# TH8_CPU_STM32F4.net
KiCad netlist of a schematic drawn in Altium Designer
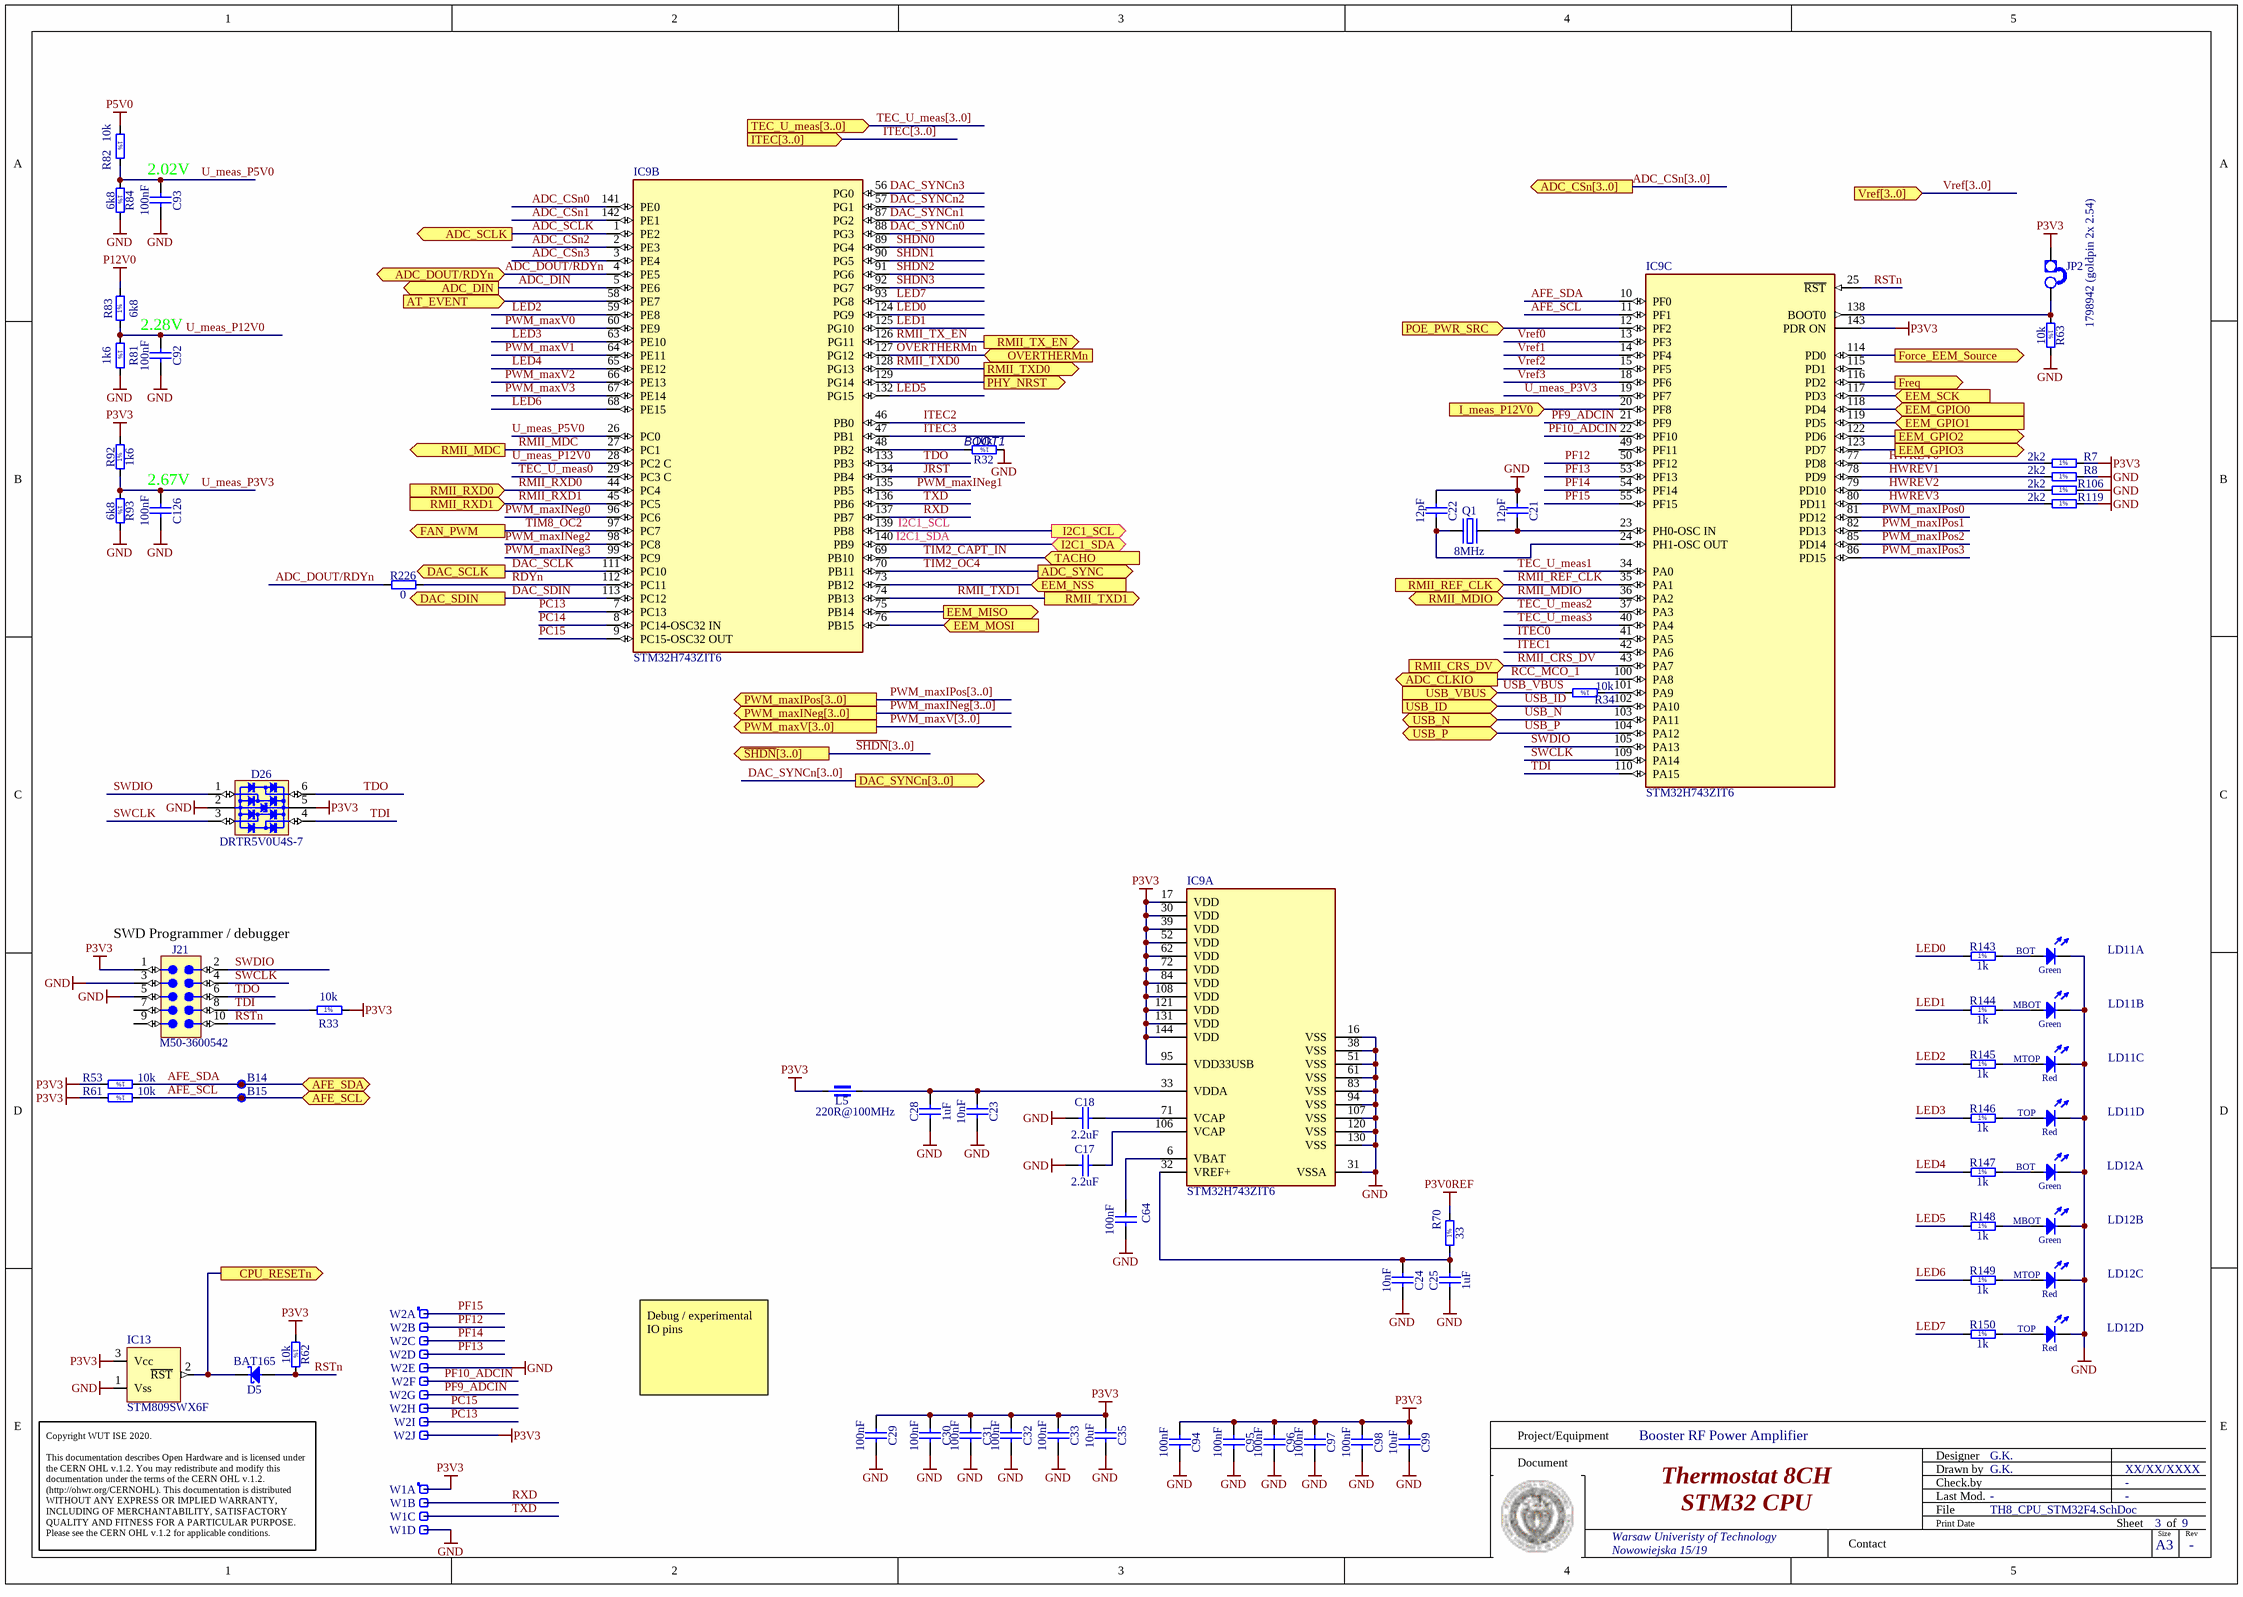
[diagram p0: TH8_CPU_STM32F4.SchDoc]

(export (version "E")
  (design (tool "Eeschema 10.0.6"))
  (components
    (comp (ref "B14")
      (value "SMD Pad")
      (footprint "C100")
      (description "Through Hole Pad")
      (fields (field (name "PART NUMBER") "SMD_PAD_D1MM") (field (name "AUTHOR") "CERN DEM JLC"))
      (libsource (lib "Eletro-mechanical") (part "Single SMD Pad (Round)"))
    )
    (comp (ref "B15")
      (value "SMD Pad")
      (footprint "C100")
      (description "Through Hole Pad")
      (fields (field (name "PART NUMBER") "SMD_PAD_D1MM") (field (name "AUTHOR") "CERN DEM JLC"))
      (libsource (lib "Eletro-mechanical") (part "Single SMD Pad (Round)"))
    )
    (comp (ref "C17")
      (value "2.2uF")
      (footprint "CAPC1608X90N")
      (description "Non-polarised capacitor")
      (fields
        (field (name "PART NUMBER") "CC0603_2.2UF_10V_20%_X7R")
        (field (name "VOLTAGE") "10V")
        (field (name "AUTHOR") "CERN DEM JLC")
      )
      (libsource (lib "Capacitors") (part "Capacitor - non polarized"))
    )
    (comp (ref "C18")
      (value "2.2uF")
      (footprint "CAPC1608X90N")
      (description "Non-polarised capacitor")
      (fields
        (field (name "PART NUMBER") "CC0603_2.2UF_10V_20%_X7R")
        (field (name "VOLTAGE") "10V")
        (field (name "AUTHOR") "CERN DEM JLC")
      )
      (libsource (lib "Capacitors") (part "Capacitor - non polarized"))
    )
    (comp (ref "C21")
      (value "12pF")
      (footprint "CAPC1005X55N")
      (description "Non-polarised capacitor")
      (fields
        (field (name "PART NUMBER") "CC0402_12PF_50V_5%_C0G")
        (field (name "VOLTAGE") "50V")
        (field (name "AUTHOR") "CERN DEM JLC")
      )
      (libsource (lib "Capacitors") (part "Capacitor - non polarized"))
    )
    (comp (ref "C22")
      (value "12pF")
      (footprint "CAPC1005X55N")
      (description "Non-polarised capacitor")
      (fields
        (field (name "PART NUMBER") "CC0402_12PF_50V_5%_C0G")
        (field (name "VOLTAGE") "50V")
        (field (name "AUTHOR") "CERN DEM JLC")
      )
      (libsource (lib "Capacitors") (part "Capacitor - non polarized"))
    )
    (comp (ref "C23")
      (value "10nF")
      (footprint "CAPC1005X55N")
      (description "Non-polarised capacitor")
      (fields
        (field (name "PART NUMBER") "CC0402_10NF_16V_10%_X7R")
        (field (name "VOLTAGE") "16V")
        (field (name "AUTHOR") "CERN DEM JLC")
      )
      (libsource (lib "Capacitors") (part "Capacitor - non polarized"))
    )
    (comp (ref "C24")
      (value "10nF")
      (footprint "CAPC1005X55N")
      (description "Non-polarised capacitor")
      (fields
        (field (name "PART NUMBER") "CC0402_10NF_16V_10%_X7R")
        (field (name "VOLTAGE") "16V")
        (field (name "AUTHOR") "CERN DEM JLC")
      )
      (libsource (lib "Capacitors") (part "Capacitor - non polarized"))
    )
    (comp (ref "C25")
      (value "1uF")
      (footprint "CAPC2012X110N")
      (description "Non-polarised capacitor")
      (fields
        (field (name "PART NUMBER") "CC0805_1UF_50V_10%_X7R")
        (field (name "VOLTAGE") "50V")
        (field (name "AUTHOR") "CERN DEM JLC")
      )
      (libsource (lib "Capacitors") (part "Capacitor - non polarized"))
    )
    (comp (ref "C28")
      (value "1uF")
      (footprint "CAPC2012X110N")
      (description "Non-polarised capacitor")
      (fields
        (field (name "PART NUMBER") "CC0805_1UF_50V_10%_X7R")
        (field (name "VOLTAGE") "50V")
        (field (name "AUTHOR") "CERN DEM JLC")
      )
      (libsource (lib "Capacitors") (part "Capacitor - non polarized"))
    )
    (comp (ref "C29")
      (value "100nF")
      (footprint "CAPC1005X55N")
      (description "Non-polarised capacitor")
      (fields
        (field (name "PART NUMBER") "CC0402_100NF_16V_10%_X7R")
        (field (name "VOLTAGE") "16V")
        (field (name "AUTHOR") "CERN DEM JLC")
      )
      (libsource (lib "Capacitors") (part "Capacitor - non polarized"))
    )
    (comp (ref "C30")
      (value "100nF")
      (footprint "CAPC1005X55N")
      (description "Non-polarised capacitor")
      (fields
        (field (name "PART NUMBER") "CC0402_100NF_16V_10%_X7R")
        (field (name "VOLTAGE") "16V")
        (field (name "AUTHOR") "CERN DEM JLC")
      )
      (libsource (lib "Capacitors") (part "Capacitor - non polarized"))
    )
    (comp (ref "C31")
      (value "100nF")
      (footprint "CAPC1005X55N")
      (description "Non-polarised capacitor")
      (fields
        (field (name "PART NUMBER") "CC0402_100NF_16V_10%_X7R")
        (field (name "VOLTAGE") "16V")
        (field (name "AUTHOR") "CERN DEM JLC")
      )
      (libsource (lib "Capacitors") (part "Capacitor - non polarized"))
    )
    (comp (ref "C32")
      (value "100nF")
      (footprint "CAPC1005X55N")
      (description "Non-polarised capacitor")
      (fields
        (field (name "PART NUMBER") "CC0402_100NF_16V_10%_X7R")
        (field (name "VOLTAGE") "16V")
        (field (name "AUTHOR") "CERN DEM JLC")
      )
      (libsource (lib "Capacitors") (part "Capacitor - non polarized"))
    )
    (comp (ref "C33")
      (value "100nF")
      (footprint "CAPC1005X55N")
      (description "Non-polarised capacitor")
      (fields
        (field (name "PART NUMBER") "CC0402_100NF_16V_10%_X7R")
        (field (name "VOLTAGE") "16V")
        (field (name "AUTHOR") "CERN DEM JLC")
      )
      (libsource (lib "Capacitors") (part "Capacitor - non polarized"))
    )
    (comp (ref "C35")
      (value "10uF")
      (footprint "CAPC2012X135N")
      (description "Non-polarised capacitor")
      (fields
        (field (name "PART NUMBER") "CC0805_10UF_16V_10%_X5R")
        (field (name "VOLTAGE") "16V")
        (field (name "AUTHOR") "CERN DEM JLC")
      )
      (libsource (lib "Capacitors") (part "Capacitor - non polarized"))
    )
    (comp (ref "C64")
      (value "100nF")
      (footprint "CAPC1005X55N")
      (description "Non-polarised capacitor")
      (fields
        (field (name "PART NUMBER") "CC0402_100NF_16V_10%_X7R")
        (field (name "VOLTAGE") "16V")
        (field (name "AUTHOR") "CERN DEM JLC")
      )
      (libsource (lib "Capacitors") (part "Capacitor - non polarized"))
    )
    (comp (ref "C92")
      (value "100nF")
      (footprint "CAPC1005X55N")
      (description "Non-polarised capacitor")
      (fields
        (field (name "PART NUMBER") "CC0402_100NF_16V_10%_X5R")
        (field (name "VOLTAGE") "16V")
        (field (name "AUTHOR") "CERN DEM JLC")
      )
      (libsource (lib "Capacitors") (part "Capacitor - non polarized"))
    )
    (comp (ref "C93")
      (value "100nF")
      (footprint "CAPC1005X55N")
      (description "Non-polarised capacitor")
      (fields
        (field (name "PART NUMBER") "CC0402_100NF_16V_10%_X5R")
        (field (name "VOLTAGE") "16V")
        (field (name "AUTHOR") "CERN DEM JLC")
      )
      (libsource (lib "Capacitors") (part "Capacitor - non polarized"))
    )
    (comp (ref "C94")
      (value "100nF")
      (footprint "CAPC1005X55N")
      (description "Non-polarised capacitor")
      (fields
        (field (name "PART NUMBER") "CC0402_100NF_16V_10%_X7R")
        (field (name "VOLTAGE") "16V")
        (field (name "AUTHOR") "CERN DEM JLC")
      )
      (libsource (lib "Capacitors") (part "Capacitor - non polarized"))
    )
    (comp (ref "C95")
      (value "100nF")
      (footprint "CAPC1005X55N")
      (description "Non-polarised capacitor")
      (fields
        (field (name "PART NUMBER") "CC0402_100NF_16V_10%_X7R")
        (field (name "VOLTAGE") "16V")
        (field (name "AUTHOR") "CERN DEM JLC")
      )
      (libsource (lib "Capacitors") (part "Capacitor - non polarized"))
    )
    (comp (ref "C96")
      (value "100nF")
      (footprint "CAPC1005X55N")
      (description "Non-polarised capacitor")
      (fields
        (field (name "PART NUMBER") "CC0402_100NF_16V_10%_X7R")
        (field (name "VOLTAGE") "16V")
        (field (name "AUTHOR") "CERN DEM JLC")
      )
      (libsource (lib "Capacitors") (part "Capacitor - non polarized"))
    )
    (comp (ref "C97")
      (value "100nF")
      (footprint "CAPC1005X55N")
      (description "Non-polarised capacitor")
      (fields
        (field (name "PART NUMBER") "CC0402_100NF_16V_10%_X7R")
        (field (name "VOLTAGE") "16V")
        (field (name "AUTHOR") "CERN DEM JLC")
      )
      (libsource (lib "Capacitors") (part "Capacitor - non polarized"))
    )
    (comp (ref "C98")
      (value "100nF")
      (footprint "CAPC1005X55N")
      (description "Non-polarised capacitor")
      (fields
        (field (name "PART NUMBER") "CC0402_100NF_16V_10%_X7R")
        (field (name "VOLTAGE") "16V")
        (field (name "AUTHOR") "CERN DEM JLC")
      )
      (libsource (lib "Capacitors") (part "Capacitor - non polarized"))
    )
    (comp (ref "C99")
      (value "10uF")
      (footprint "CAPC2012X135N")
      (description "Non-polarised capacitor")
      (fields
        (field (name "PART NUMBER") "CC0805_10UF_16V_10%_X5R")
        (field (name "VOLTAGE") "16V")
        (field (name "AUTHOR") "CERN DEM JLC")
      )
      (libsource (lib "Capacitors") (part "Capacitor - non polarized"))
    )
    (comp (ref "C126")
      (value "100nF")
      (footprint "CAPC1005X55N")
      (description "Non-polarised capacitor")
      (fields
        (field (name "PART NUMBER") "CC0402_100NF_16V_10%_X5R")
        (field (name "VOLTAGE") "16V")
        (field (name "AUTHOR") "CERN DEM JLC")
      )
      (libsource (lib "Capacitors") (part "Capacitor - non polarized"))
    )
    (comp (ref "D5")
      (value "BAT165")
      (footprint "SOD2512X110N")
      (description "Schottky Diode")
      (fields
        (field (name "VOLTAGE") "40V")
        (field (name "POWER") "750mA")
        (field (name "AUTHOR") "CERN DEM JLC")
      )
      (libsource (lib "ICs And Semiconductors") (part "Diode Schottky"))
    )
    (comp (ref "D26")
      (value "DRTR5V0U4S-7")
      (footprint "SOT65P210X110-6N")
      (description "Integrated Quad Ultra-Low Capacitance ESD Protection")
      (fields (field (name "MANUFACTURER") "DIODES") (field (name "AUTHOR") "GK"))
      (libsource (lib "Diodes") (part "D_TVS_DRTR5V0U4S-7"))
    )
    (comp (ref "IC9")
      (value "STM32H743ZIT6")
      (footprint "FP-LQFP144-1A-MFG")
      (description "IC MCU 32BIT 2MB FLASH 144LQFP")
      (fields
        (field (name "MANUFACTURER") "STMicroelectronics")
        (field (name "OCTOPART") "https://octopart.com/stm32h743zit6-stmicroelectronics-76372529")
      )
      (libsource (lib "Altium Content Vault") (part "4977c5c7f8d170b58ef15f889e64ba1"))
    )
    (comp (ref "IC13")
      (value "STM809SWX6F")
      (footprint "SOT-23")
      (description "2.93V  Reset circuit")
      (libsource (lib "LIBRARY_SCH") (part "VMON_STM809"))
    )
    (comp (ref "J21")
      (value "Header 10")
      (footprint "HARWIN_M50-3600542")
      (description "10 Contacts - Pitch 1.27mm - Dual Row SMT Vertical Pin Header (Post Lead = 3mm, Insulator 1mm)")
      (fields
        (field (name "PART NUMBER") "HARWIN_M50-3600542")
        (field (name "MANUFACTURER") "HARWIN")
        (field (name "MANUFACTURER PART NUMBER") "M50-3600542")
        (field (name "AUTHOR") "GK")
      )
      (libsource (lib "Connectors") (part "CON_2x10 1.27 SMT_male_HARWIN"))
    )
    (comp (ref "JP2")
      (value "1798942 (goldpin 2x 2.54)")
      (footprint "jump")
      (description "Jumper")
      (libsource (lib "LIBRARY_SCH") (part "JUMPER"))
    )
    (comp (ref "L5")
      (value "220R@100MHz")
      (footprint "INDC1005X55N")
      (fields
        (field (name "PART NUMBER") "IND0402_MURATA_BLM15HB221SN1")
        (field (name "POWER") "250mA")
        (field (name "TOLERANCE") "±25%")
        (field (name "AUTHOR") "CERN DEM JLC")
      )
      (libsource (lib "Inductors & Transformers") (part "Ferrite Bead"))
    )
    (comp (ref "LD11")
      (value "Green/Green/HeRed/HeRed")
      (footprint "LED_BIVAR_H485CHHGGDL")
      (description "LED x4 G-1C2A-BOT_G-3C4A_H-5C6A_H-7C8A-TOP")
      (fields
        (field (name "PART NUMBER") "LED_BIVAR_H485CHHGGDL")
        (field (name "MANUFACTURER") "BIVAR")
        (field (name "AUTHOR") "CERN DEM BC")
      )
      (libsource (lib "ICs And Semiconductors") (part "LED x4 G-1C2A-BOT_G-3C4A_H-5C6A_H-7C8A-TOP"))
    )
    (comp (ref "LD12")
      (value "Green/Green/HeRed/HeRed")
      (footprint "LED_BIVAR_H485CHHGGDL")
      (description "LED x4 G-1C2A-BOT_G-3C4A_H-5C6A_H-7C8A-TOP")
      (fields
        (field (name "PART NUMBER") "LED_BIVAR_H485CHHGGDL")
        (field (name "MANUFACTURER") "BIVAR")
        (field (name "AUTHOR") "CERN DEM BC")
      )
      (libsource (lib "ICs And Semiconductors") (part "LED x4 G-1C2A-BOT_G-3C4A_H-5C6A_H-7C8A-TOP"))
    )
    (comp (ref "Q1")
      (value "8MHz")
      (footprint "XTAL_TXC_7A")
      (description "Quartz Crystal")
      (fields
        (field (name "PART NUMBER") "XTAL_8MHZ_TXC_7A-8.000MAAE-T")
        (field (name "MANUFACTURER") "TXC CORPORATION")
        (field (name "AUTHOR") "CERN DEM JLC")
      )
      (libsource (lib "ICs And Semiconductors") (part "Quartz Crystal"))
    )
    (comp (ref "R7")
      (value "2k2")
      (footprint "RESC1005X40N")
      (description "Resistor - 1%")
      (fields
        (field (name "PART NUMBER") "R0402_2K2_1%_0.0625W_100PPM")
        (field (name "POWER") "0.0625W")
        (field (name "AUTHOR") "CERN DEM JLC")
      )
      (libsource (lib "Resistors") (part "Resistor - 1%"))
    )
    (comp (ref "R8")
      (value "2k2")
      (footprint "RESC1005X40N")
      (description "Resistor - 1%")
      (fields
        (field (name "PART NUMBER") "R0402_2K2_1%_0.0625W_100PPM")
        (field (name "POWER") "0.0625W")
        (field (name "AUTHOR") "CERN DEM JLC")
      )
      (libsource (lib "Resistors") (part "Resistor - 1%"))
    )
    (comp (ref "R32")
      (value "10k")
      (footprint "RESC1005X40N")
      (description "Resistor - 1%")
      (fields
        (field (name "PART NUMBER") "R0402_10K_1%_0.0625W_100PPM")
        (field (name "POWER") "0.0625W")
        (field (name "AUTHOR") "CERN DEM JLC")
      )
      (libsource (lib "Resistors") (part "Resistor - 1%"))
    )
    (comp (ref "R33")
      (value "10k")
      (footprint "RESC1005X40N")
      (description "Resistor - 1%")
      (fields
        (field (name "PART NUMBER") "R0402_10K_1%_0.0625W_100PPM")
        (field (name "POWER") "0.0625W")
        (field (name "AUTHOR") "CERN DEM JLC")
      )
      (libsource (lib "Resistors") (part "Resistor - 1%"))
    )
    (comp (ref "R34")
      (value "10k")
      (footprint "RESC1005X40N")
      (description "Resistor - 1%")
      (fields
        (field (name "PART NUMBER") "R0402_10K_1%_0.0625W_100PPM")
        (field (name "POWER") "0.0625W")
        (field (name "AUTHOR") "CERN DEM JLC")
      )
      (libsource (lib "Resistors") (part "Resistor - 1%"))
    )
    (comp (ref "R53")
      (value "10k")
      (footprint "RESC1005X40N")
      (description "Resistor - 1%")
      (fields
        (field (name "PART NUMBER") "R0402_10K_1%_0.0625W_100PPM")
        (field (name "POWER") "0.0625W")
        (field (name "AUTHOR") "CERN DEM JLC")
      )
      (libsource (lib "Resistors") (part "Resistor - 1%"))
    )
    (comp (ref "R61")
      (value "10k")
      (footprint "RESC1005X40N")
      (description "Resistor - 1%")
      (fields
        (field (name "PART NUMBER") "R0402_10K_1%_0.0625W_100PPM")
        (field (name "POWER") "0.0625W")
        (field (name "AUTHOR") "CERN DEM JLC")
      )
      (libsource (lib "Resistors") (part "Resistor - 1%"))
    )
    (comp (ref "R62")
      (value "10k")
      (footprint "RESC1005X40N")
      (description "Resistor - 1%")
      (fields
        (field (name "PART NUMBER") "R0402_10K_1%_0.0625W_100PPM")
        (field (name "POWER") "0.0625W")
        (field (name "AUTHOR") "CERN DEM JLC")
      )
      (libsource (lib "Resistors") (part "Resistor - 1%"))
    )
    (comp (ref "R63")
      (value "10k")
      (footprint "RESC1005X40N")
      (description "Resistor - 1%")
      (fields
        (field (name "PART NUMBER") "R0402_10K_1%_0.0625W_100PPM")
        (field (name "POWER") "0.0625W")
        (field (name "AUTHOR") "CERN DEM JLC")
      )
      (libsource (lib "Resistors") (part "Resistor - 1%"))
    )
    (comp (ref "R70")
      (value "33")
      (footprint "RESC1005X40N")
      (description "Resistor - 1%")
      (fields
        (field (name "PART NUMBER") "R0402_33R_1%_0.0625W_100PPM")
        (field (name "POWER") "0.0625W")
        (field (name "AUTHOR") "CERN DEM JLC")
      )
      (libsource (lib "Resistors") (part "Resistor - 1%"))
    )
    (comp (ref "R81")
      (value "1k6")
      (footprint "RESC1005X40N")
      (description "Resistor - 1%")
      (fields
        (field (name "PART NUMBER") "R0402_1K6_1%_0.0625W_100PPM")
        (field (name "POWER") "0.0625W")
        (field (name "AUTHOR") "CERN DEM JLC")
      )
      (libsource (lib "Resistors") (part "Resistor - 1%"))
    )
    (comp (ref "R82")
      (value "10k")
      (footprint "RESC1005X40N")
      (description "Resistor - 1%")
      (fields
        (field (name "PART NUMBER") "R0402_10K_1%_0.0625W_100PPM")
        (field (name "POWER") "0.0625W")
        (field (name "AUTHOR") "CERN DEM JLC")
      )
      (libsource (lib "Resistors") (part "Resistor - 1%"))
    )
    (comp (ref "R83")
      (value "6k8")
      (footprint "RESC1005X40N")
      (description "Resistor - 1%")
      (fields
        (field (name "PART NUMBER") "R0402_6K8_1%_0.0625W_100PPM")
        (field (name "POWER") "0.0625W")
        (field (name "AUTHOR") "CERN DEM JLC")
      )
      (libsource (lib "Resistors") (part "Resistor - 1%"))
    )
    (comp (ref "R84")
      (value "6k8")
      (footprint "RESC1005X40N")
      (description "Resistor - 1%")
      (fields
        (field (name "PART NUMBER") "R0402_6K8_1%_0.0625W_100PPM")
        (field (name "POWER") "0.0625W")
        (field (name "AUTHOR") "CERN DEM JLC")
      )
      (libsource (lib "Resistors") (part "Resistor - 1%"))
    )
    (comp (ref "R92")
      (value "1k6")
      (footprint "RESC1005X40N")
      (description "Resistor - 1%")
      (fields
        (field (name "PART NUMBER") "R0402_1K6_1%_0.0625W_100PPM")
        (field (name "POWER") "0.0625W")
        (field (name "AUTHOR") "CERN DEM JLC")
      )
      (libsource (lib "Resistors") (part "Resistor - 1%"))
    )
    (comp (ref "R93")
      (value "6k8")
      (footprint "RESC1005X40N")
      (description "Resistor - 1%")
      (fields
        (field (name "PART NUMBER") "R0402_6K8_1%_0.0625W_100PPM")
        (field (name "POWER") "0.0625W")
        (field (name "AUTHOR") "CERN DEM JLC")
      )
      (libsource (lib "Resistors") (part "Resistor - 1%"))
    )
    (comp (ref "R106")
      (value "2k2")
      (footprint "RESC1005X40N")
      (description "Resistor - 1%")
      (fields
        (field (name "PART NUMBER") "R0402_2K2_1%_0.0625W_100PPM")
        (field (name "POWER") "0.0625W")
        (field (name "AUTHOR") "CERN DEM JLC")
      )
      (libsource (lib "Resistors") (part "Resistor - 1%"))
    )
    (comp (ref "R119")
      (value "2k2")
      (footprint "RESC1005X40N")
      (description "Resistor - 1%")
      (fields
        (field (name "PART NUMBER") "R0402_2K2_1%_0.0625W_100PPM")
        (field (name "POWER") "0.0625W")
        (field (name "AUTHOR") "CERN DEM JLC")
      )
      (libsource (lib "Resistors") (part "Resistor - 1%"))
    )
    (comp (ref "R143")
      (value "1k")
      (footprint "RESC1005X40N")
      (description "Resistor - 1%")
      (fields
        (field (name "PART NUMBER") "R0402_1K_1%_0.0625W_100PPM")
        (field (name "POWER") "0.0625W")
        (field (name "AUTHOR") "CERN DEM JLC")
      )
      (libsource (lib "Resistors") (part "Resistor - 1%"))
    )
    (comp (ref "R144")
      (value "1k")
      (footprint "RESC1005X40N")
      (description "Resistor - 1%")
      (fields
        (field (name "PART NUMBER") "R0402_1K_1%_0.0625W_100PPM")
        (field (name "POWER") "0.0625W")
        (field (name "AUTHOR") "CERN DEM JLC")
      )
      (libsource (lib "Resistors") (part "Resistor - 1%"))
    )
    (comp (ref "R145")
      (value "1k")
      (footprint "RESC1005X40N")
      (description "Resistor - 1%")
      (fields
        (field (name "PART NUMBER") "R0402_1K_1%_0.0625W_100PPM")
        (field (name "POWER") "0.0625W")
        (field (name "AUTHOR") "CERN DEM JLC")
      )
      (libsource (lib "Resistors") (part "Resistor - 1%"))
    )
    (comp (ref "R146")
      (value "1k")
      (footprint "RESC1005X40N")
      (description "Resistor - 1%")
      (fields
        (field (name "PART NUMBER") "R0402_1K_1%_0.0625W_100PPM")
        (field (name "POWER") "0.0625W")
        (field (name "AUTHOR") "CERN DEM JLC")
      )
      (libsource (lib "Resistors") (part "Resistor - 1%"))
    )
    (comp (ref "R147")
      (value "1k")
      (footprint "RESC1005X40N")
      (description "Resistor - 1%")
      (fields
        (field (name "PART NUMBER") "R0402_1K_1%_0.0625W_100PPM")
        (field (name "POWER") "0.0625W")
        (field (name "AUTHOR") "CERN DEM JLC")
      )
      (libsource (lib "Resistors") (part "Resistor - 1%"))
    )
    (comp (ref "R148")
      (value "1k")
      (footprint "RESC1005X40N")
      (description "Resistor - 1%")
      (fields
        (field (name "PART NUMBER") "R0402_1K_1%_0.0625W_100PPM")
        (field (name "POWER") "0.0625W")
        (field (name "AUTHOR") "CERN DEM JLC")
      )
      (libsource (lib "Resistors") (part "Resistor - 1%"))
    )
    (comp (ref "R149")
      (value "1k")
      (footprint "RESC1005X40N")
      (description "Resistor - 1%")
      (fields
        (field (name "PART NUMBER") "R0402_1K_1%_0.0625W_100PPM")
        (field (name "POWER") "0.0625W")
        (field (name "AUTHOR") "CERN DEM JLC")
      )
      (libsource (lib "Resistors") (part "Resistor - 1%"))
    )
    (comp (ref "R150")
      (value "1k")
      (footprint "RESC1005X40N")
      (description "Resistor - 1%")
      (fields
        (field (name "PART NUMBER") "R0402_1K_1%_0.0625W_100PPM")
        (field (name "POWER") "0.0625W")
        (field (name "AUTHOR") "CERN DEM JLC")
      )
      (libsource (lib "Resistors") (part "Resistor - 1%"))
    )
    (comp (ref "R226")
      (value "0")
      (footprint "RESC1005X40N")
      (description "Resistor")
      (fields
        (field (name "PART NUMBER") "R0402_0R_JUMPER")
        (field (name "MANUFACTURER") "GENERIC")
        (field (name "AUTHOR") "CERN DEM JLC")
      )
      (libsource (lib "Resistors") (part "Resistor"))
    )
    (comp (ref "W1")
      (value "Header 4")
      (footprint "SAMTEC_HTSW-104-23-L-S")
      (description "4 Mini Wire-Wrap Contact Strip Header")
      (fields
        (field (name "PART NUMBER") "SAMTEC_HTSW-104-23-L-S")
        (field (name "MANUFACTURER") "SAMTEC")
        (field (name "AUTHOR") "CERN DEM JLC")
      )
      (libsource (lib "Connectors") (part "Wire-Wrap Contact x4"))
    )
    (comp (ref "W2")
      (value "Header 10")
      (footprint "SAMTEC_MTLW-110-07-L-S-250")
      (description "10 Mini Wire-Wrap Contact Strip Header")
      (fields
        (field (name "PART NUMBER") "SAMTEC_MTLW-110-07-L-S-250")
        (field (name "MANUFACTURER") "SAMTEC")
        (field (name "AUTHOR") "CERN DEM JLC")
      )
      (libsource (lib "Connectors") (part "Wire-Wrap Contact x10"))
    )
  )
  (nets
    (net (code "1") (name "/ADC_CSn0") (class "Default")
      (node (ref "IC9") (pin "141") (pinfunction "PE0_141") (pintype "bidirectional"))
    )
    (net (code "2") (name "/ADC_CSn1") (class "Default")
      (node (ref "IC9") (pin "142") (pinfunction "PE1_142") (pintype "bidirectional"))
    )
    (net (code "3") (name "/ADC_CSn2") (class "Default")
      (node (ref "IC9") (pin "2") (pinfunction "PE3_2") (pintype "bidirectional"))
    )
    (net (code "4") (name "/ADC_CSn3") (class "Default")
      (node (ref "IC9") (pin "3") (pinfunction "PE4_3") (pintype "bidirectional"))
    )
    (net (code "6") (name "/ADC_DIN") (class "Default")
      (node (ref "IC9") (pin "5") (pinfunction "PE6_5") (pintype "bidirectional"))
    )
    (net (code "7") (name "/ADC_DOUT{slash}RDYn") (class "Default")
      (node (ref "IC9") (pin "4") (pinfunction "PE5_4") (pintype "bidirectional"))
      (node (ref "R226") (pin "1") (pinfunction "1_1") (pintype "passive"))
    )
    (net (code "8") (name "/ADC_SCLK") (class "Default")
      (node (ref "IC9") (pin "1") (pinfunction "PE2_1") (pintype "bidirectional"))
    )
    (net (code "9") (name "/AFE_SCL") (class "Default")
      (node (ref "B15") (pin "1") (pinfunction "1_1") (pintype "bidirectional"))
      (node (ref "IC9") (pin "11") (pinfunction "PF1_11") (pintype "bidirectional"))
      (node (ref "R61") (pin "1") (pinfunction "1_1") (pintype "passive"))
    )
    (net (code "10") (name "/AFE_SDA") (class "Default")
      (node (ref "B14") (pin "1") (pinfunction "1_1") (pintype "bidirectional"))
      (node (ref "IC9") (pin "10") (pinfunction "PF0_10") (pintype "bidirectional"))
      (node (ref "R53") (pin "1") (pinfunction "1_1") (pintype "passive"))
    )
    (net (code "11") (name "/AT_EVENT") (class "Default")
      (node (ref "IC9") (pin "58") (pinfunction "PE7_58") (pintype "bidirectional"))
    )
    (net (code "12") (name "/CPU_RESETn") (class "Default")
      (node (ref "D5") (pin "1") (pinfunction "C_1") (pintype "passive"))
      (node (ref "IC13") (pin "2") (pinfunction "~{RST}_2") (pintype "output"))
    )
    (net (code "13") (name "/DAC_SCLK") (class "Default")
      (node (ref "IC9") (pin "111") (pinfunction "PC10_111") (pintype "bidirectional"))
    )
    (net (code "14") (name "/DAC_SDIN") (class "Default")
      (node (ref "IC9") (pin "113") (pinfunction "PC12_113") (pintype "bidirectional"))
    )
    (net (code "15") (name "/DAC_SYNCn0") (class "Default")
      (node (ref "IC9") (pin "88") (pinfunction "PG3_88") (pintype "bidirectional"))
    )
    (net (code "16") (name "/DAC_SYNCn1") (class "Default")
      (node (ref "IC9") (pin "87") (pinfunction "PG2_87") (pintype "bidirectional"))
    )
    (net (code "17") (name "/DAC_SYNCn2") (class "Default")
      (node (ref "IC9") (pin "57") (pinfunction "PG1_57") (pintype "bidirectional"))
    )
    (net (code "18") (name "/DAC_SYNCn3") (class "Default")
      (node (ref "IC9") (pin "56") (pinfunction "PG0_56") (pintype "bidirectional"))
    )
    (net (code "20") (name "/EEM_GPIO0") (class "Default")
      (node (ref "IC9") (pin "118") (pinfunction "PD4_118") (pintype "bidirectional"))
    )
    (net (code "21") (name "/EEM_GPIO1") (class "Default")
      (node (ref "IC9") (pin "119") (pinfunction "PD5_119") (pintype "bidirectional"))
    )
    (net (code "22") (name "/EEM_GPIO2") (class "Default")
      (node (ref "IC9") (pin "122") (pinfunction "PD6_122") (pintype "bidirectional"))
    )
    (net (code "23") (name "/EEM_GPIO3") (class "Default")
      (node (ref "IC9") (pin "123") (pinfunction "PD7_123") (pintype "bidirectional"))
    )
    (net (code "24") (name "/EEM_MISO") (class "Default")
      (node (ref "IC9") (pin "75") (pinfunction "PB14_75") (pintype "bidirectional"))
    )
    (net (code "25") (name "/EEM_MOSI") (class "Default")
      (node (ref "IC9") (pin "76") (pinfunction "PB15_76") (pintype "bidirectional"))
    )
    (net (code "26") (name "/EEM_NSS") (class "Default")
      (node (ref "IC9") (pin "73") (pinfunction "PB12_73") (pintype "bidirectional"))
    )
    (net (code "27") (name "/EEM_SCK") (class "Default")
      (node (ref "IC9") (pin "117") (pinfunction "PD3_117") (pintype "bidirectional"))
    )
    (net (code "28") (name "/Force_EEM_Source") (class "Default")
      (node (ref "IC9") (pin "114") (pinfunction "PD0_114") (pintype "bidirectional"))
    )
    (net (code "29") (name "/Freq") (class "Default")
      (node (ref "IC9") (pin "116") (pinfunction "PD2_116") (pintype "bidirectional"))
    )
    (net (code "30") (name "/HWREV0") (class "Default")
      (node (ref "IC9") (pin "77") (pinfunction "PD8_77") (pintype "bidirectional"))
      (node (ref "R7") (pin "1") (pinfunction "1_1") (pintype "passive"))
    )
    (net (code "31") (name "/HWREV1") (class "Default")
      (node (ref "IC9") (pin "78") (pinfunction "PD9_78") (pintype "bidirectional"))
      (node (ref "R8") (pin "1") (pinfunction "1_1") (pintype "passive"))
    )
    (net (code "32") (name "/HWREV2") (class "Default")
      (node (ref "IC9") (pin "79") (pinfunction "PD10_79") (pintype "bidirectional"))
      (node (ref "R106") (pin "1") (pinfunction "1_1") (pintype "passive"))
    )
    (net (code "33") (name "/HWREV3") (class "Default")
      (node (ref "IC9") (pin "80") (pinfunction "PD11_80") (pintype "bidirectional"))
      (node (ref "R119") (pin "1") (pinfunction "1_1") (pintype "passive"))
    )
    (net (code "34") (name "/I2C1_SCL") (class "Default")
      (node (ref "IC9") (pin "139") (pinfunction "PB8_139") (pintype "bidirectional"))
    )
    (net (code "35") (name "/I2C1_SDA") (class "Default")
      (node (ref "IC9") (pin "140") (pinfunction "PB9_140") (pintype "bidirectional"))
    )
    (net (code "36") (name "/ITEC0") (class "Default")
      (node (ref "IC9") (pin "41") (pinfunction "PA5_41") (pintype "bidirectional"))
    )
    (net (code "37") (name "/ITEC1") (class "Default")
      (node (ref "IC9") (pin "42") (pinfunction "PA6_42") (pintype "bidirectional"))
    )
    (net (code "38") (name "/ITEC2") (class "Default")
      (node (ref "IC9") (pin "46") (pinfunction "PB0_46") (pintype "bidirectional"))
    )
    (net (code "39") (name "/ITEC3") (class "Default")
      (node (ref "IC9") (pin "47") (pinfunction "PB1_47") (pintype "bidirectional"))
    )
    (net (code "41") (name "/I_meas_P12V0") (class "Default")
      (node (ref "IC9") (pin "20") (pinfunction "PF8_20") (pintype "bidirectional"))
    )
    (net (code "42") (name "/JRST") (class "Default")
      (node (ref "IC9") (pin "134") (pinfunction "PB4_134") (pintype "bidirectional"))
    )
    (net (code "43") (name "/LED0") (class "Default")
      (node (ref "IC9") (pin "124") (pinfunction "PG9_124") (pintype "bidirectional"))
      (node (ref "R143") (pin "1") (pinfunction "1_1") (pintype "passive"))
    )
    (net (code "44") (name "/LED1") (class "Default")
      (node (ref "IC9") (pin "125") (pinfunction "PG10_125") (pintype "bidirectional"))
      (node (ref "R144") (pin "1") (pinfunction "1_1") (pintype "passive"))
    )
    (net (code "45") (name "/LED2") (class "Default")
      (node (ref "IC9") (pin "59") (pinfunction "PE8_59") (pintype "bidirectional"))
      (node (ref "R145") (pin "1") (pinfunction "1_1") (pintype "passive"))
    )
    (net (code "46") (name "/LED3") (class "Default")
      (node (ref "IC9") (pin "63") (pinfunction "PE10_63") (pintype "bidirectional"))
      (node (ref "R146") (pin "1") (pinfunction "1_1") (pintype "passive"))
    )
    (net (code "47") (name "/LED4") (class "Default")
      (node (ref "IC9") (pin "65") (pinfunction "PE12_65") (pintype "bidirectional"))
      (node (ref "R147") (pin "1") (pinfunction "1_1") (pintype "passive"))
    )
    (net (code "48") (name "/LED5") (class "Default")
      (node (ref "IC9") (pin "132") (pinfunction "PG15_132") (pintype "bidirectional"))
      (node (ref "R148") (pin "1") (pinfunction "1_1") (pintype "passive"))
    )
    (net (code "49") (name "/LED6") (class "Default")
      (node (ref "IC9") (pin "68") (pinfunction "PE15_68") (pintype "bidirectional"))
      (node (ref "R149") (pin "1") (pinfunction "1_1") (pintype "passive"))
    )
    (net (code "50") (name "/LED7") (class "Default")
      (node (ref "IC9") (pin "93") (pinfunction "PG8_93") (pintype "bidirectional"))
      (node (ref "R150") (pin "1") (pinfunction "1_1") (pintype "passive"))
    )
    (net (code "51") (name "/OVERTHERMn") (class "Default")
      (node (ref "IC9") (pin "127") (pinfunction "PG12_127") (pintype "bidirectional"))
    )
    (net (code "52") (name "/PC13") (class "Default")
      (node (ref "IC9") (pin "7") (pinfunction "PC13_7") (pintype "bidirectional"))
      (node (ref "W2") (pin "9") (pinfunction "9_9") (pintype "bidirectional"))
    )
    (net (code "53") (name "/PC14") (class "Default")
      (node (ref "IC9") (pin "8") (pinfunction "PC14-OSC32_IN_8") (pintype "bidirectional"))
    )
    (net (code "54") (name "/PC15") (class "Default")
      (node (ref "IC9") (pin "9") (pinfunction "PC15-OSC32_OUT_9") (pintype "bidirectional"))
      (node (ref "W2") (pin "8") (pinfunction "8_8") (pintype "bidirectional"))
    )
    (net (code "55") (name "/PF9_ADCIN") (class "Default")
      (node (ref "IC9") (pin "21") (pinfunction "PF9_21") (pintype "bidirectional"))
      (node (ref "W2") (pin "7") (pinfunction "7_7") (pintype "bidirectional"))
    )
    (net (code "56") (name "/PF10_ADCIN") (class "Default")
      (node (ref "IC9") (pin "22") (pinfunction "PF10_22") (pintype "bidirectional"))
      (node (ref "W2") (pin "6") (pinfunction "6_6") (pintype "bidirectional"))
    )
    (net (code "57") (name "/PF12") (class "Default")
      (node (ref "IC9") (pin "50") (pinfunction "PF12_50") (pintype "bidirectional"))
      (node (ref "W2") (pin "2") (pinfunction "2_2") (pintype "bidirectional"))
    )
    (net (code "58") (name "/PF13") (class "Default")
      (node (ref "IC9") (pin "53") (pinfunction "PF13_53") (pintype "bidirectional"))
      (node (ref "W2") (pin "4") (pinfunction "4_4") (pintype "bidirectional"))
    )
    (net (code "59") (name "/PF14") (class "Default")
      (node (ref "IC9") (pin "54") (pinfunction "PF14_54") (pintype "bidirectional"))
      (node (ref "W2") (pin "3") (pinfunction "3_3") (pintype "bidirectional"))
    )
    (net (code "60") (name "/PF15") (class "Default")
      (node (ref "IC9") (pin "55") (pinfunction "PF15_55") (pintype "bidirectional"))
      (node (ref "W2") (pin "1") (pinfunction "1_1") (pintype "bidirectional"))
    )
    (net (code "61") (name "/PHY_NRST") (class "Default")
      (node (ref "IC9") (pin "129") (pinfunction "PG14_129") (pintype "bidirectional"))
    )
    (net (code "62") (name "/POE_PWR_SRC") (class "Default")
      (node (ref "IC9") (pin "12") (pinfunction "PF2_12") (pintype "bidirectional"))
    )
    (net (code "63") (name "/PWM_maxINeg0") (class "Default")
      (node (ref "IC9") (pin "96") (pinfunction "PC6_96") (pintype "bidirectional"))
    )
    (net (code "64") (name "/PWM_maxINeg1") (class "Default")
      (node (ref "IC9") (pin "135") (pinfunction "PB5_135") (pintype "bidirectional"))
    )
    (net (code "65") (name "/PWM_maxINeg2") (class "Default")
      (node (ref "IC9") (pin "98") (pinfunction "PC8_98") (pintype "bidirectional"))
    )
    (net (code "66") (name "/PWM_maxINeg3") (class "Default")
      (node (ref "IC9") (pin "99") (pinfunction "PC9_99") (pintype "bidirectional"))
    )
    (net (code "68") (name "/PWM_maxIPos0") (class "Default")
      (node (ref "IC9") (pin "81") (pinfunction "PD12_81") (pintype "bidirectional"))
    )
    (net (code "69") (name "/PWM_maxIPos1") (class "Default")
      (node (ref "IC9") (pin "82") (pinfunction "PD13_82") (pintype "bidirectional"))
    )
    (net (code "70") (name "/PWM_maxIPos2") (class "Default")
      (node (ref "IC9") (pin "85") (pinfunction "PD14_85") (pintype "bidirectional"))
    )
    (net (code "71") (name "/PWM_maxIPos3") (class "Default")
      (node (ref "IC9") (pin "86") (pinfunction "PD15_86") (pintype "bidirectional"))
    )
    (net (code "73") (name "/PWM_maxV0") (class "Default")
      (node (ref "IC9") (pin "60") (pinfunction "PE9_60") (pintype "bidirectional"))
    )
    (net (code "74") (name "/PWM_maxV1") (class "Default")
      (node (ref "IC9") (pin "64") (pinfunction "PE11_64") (pintype "bidirectional"))
    )
    (net (code "75") (name "/PWM_maxV2") (class "Default")
      (node (ref "IC9") (pin "66") (pinfunction "PE13_66") (pintype "bidirectional"))
    )
    (net (code "76") (name "/PWM_maxV3") (class "Default")
      (node (ref "IC9") (pin "67") (pinfunction "PE14_67") (pintype "bidirectional"))
    )
    (net (code "78") (name "/RCC_MCO_1") (class "Default")
      (node (ref "IC9") (pin "100") (pinfunction "PA8_100") (pintype "bidirectional"))
    )
    (net (code "79") (name "/RDYn") (class "Default")
      (node (ref "IC9") (pin "112") (pinfunction "PC11_112") (pintype "bidirectional"))
      (node (ref "R226") (pin "2") (pinfunction "2_2") (pintype "passive"))
    )
    (net (code "80") (name "/RMII_CRS_DV") (class "Default")
      (node (ref "IC9") (pin "43") (pinfunction "PA7_43") (pintype "bidirectional"))
    )
    (net (code "81") (name "/RMII_MDC") (class "Default")
      (node (ref "IC9") (pin "27") (pinfunction "PC1_27") (pintype "bidirectional"))
    )
    (net (code "82") (name "/RMII_MDIO") (class "Default")
      (node (ref "IC9") (pin "36") (pinfunction "PA2_36") (pintype "bidirectional"))
    )
    (net (code "83") (name "/RMII_REF_CLK") (class "Default")
      (node (ref "IC9") (pin "35") (pinfunction "PA1_35") (pintype "bidirectional"))
    )
    (net (code "84") (name "/RMII_RXD0") (class "Default")
      (node (ref "IC9") (pin "44") (pinfunction "PC4_44") (pintype "bidirectional"))
    )
    (net (code "85") (name "/RMII_RXD1") (class "Default")
      (node (ref "IC9") (pin "45") (pinfunction "PC5_45") (pintype "bidirectional"))
    )
    (net (code "86") (name "/RMII_TXD0") (class "Default")
      (node (ref "IC9") (pin "128") (pinfunction "PG13_128") (pintype "bidirectional"))
    )
    (net (code "87") (name "/RMII_TXD1") (class "Default")
      (node (ref "IC9") (pin "74") (pinfunction "PB13_74") (pintype "bidirectional"))
    )
    (net (code "88") (name "/RMII_TX_EN") (class "Default")
      (node (ref "IC9") (pin "126") (pinfunction "PG11_126") (pintype "bidirectional"))
    )
    (net (code "89") (name "/RSTn") (class "Default")
      (node (ref "D5") (pin "2") (pinfunction "A_2") (pintype "passive"))
      (node (ref "IC9") (pin "25") (pinfunction "~{RST}_25") (pintype "input"))
      (node (ref "J21") (pin "10") (pinfunction "10_10") (pintype "bidirectional"))
      (node (ref "R62") (pin "2") (pinfunction "2_2") (pintype "passive"))
    )
    (net (code "90") (name "/RXD") (class "Default")
      (node (ref "IC9") (pin "137") (pinfunction "PB7_137") (pintype "bidirectional"))
      (node (ref "W1") (pin "2") (pinfunction "2_2") (pintype "bidirectional"))
    )
    (net (code "91") (name "/SWCLK") (class "Default")
      (node (ref "D26") (pin "3") (pinfunction "I/O2_3") (pintype "bidirectional"))
      (node (ref "IC9") (pin "109") (pinfunction "PA14_109") (pintype "bidirectional"))
      (node (ref "J21") (pin "4") (pinfunction "4_4") (pintype "bidirectional"))
    )
    (net (code "92") (name "/SWDIO") (class "Default")
      (node (ref "D26") (pin "1") (pinfunction "I/O1_1") (pintype "bidirectional"))
      (node (ref "IC9") (pin "105") (pinfunction "PA13_105") (pintype "bidirectional"))
      (node (ref "J21") (pin "2") (pinfunction "2_2") (pintype "bidirectional"))
    )
    (net (code "93") (name "/TDI") (class "Default")
      (node (ref "D26") (pin "4") (pinfunction "I/O3_4") (pintype "bidirectional"))
      (node (ref "IC9") (pin "110") (pinfunction "PA15_110") (pintype "bidirectional"))
      (node (ref "J21") (pin "8") (pinfunction "8_8") (pintype "bidirectional"))
      (node (ref "R33") (pin "1") (pinfunction "1_1") (pintype "passive"))
    )
    (net (code "94") (name "/TDO") (class "Default")
      (node (ref "D26") (pin "6") (pinfunction "I/O4_6") (pintype "bidirectional"))
      (node (ref "IC9") (pin "133") (pinfunction "PB3_133") (pintype "bidirectional"))
      (node (ref "J21") (pin "6") (pinfunction "6_6") (pintype "bidirectional"))
    )
    (net (code "95") (name "/TEC_U_meas0") (class "Default")
      (node (ref "IC9") (pin "29") (pinfunction "PC3_C_29") (pintype "bidirectional"))
    )
    (net (code "96") (name "/TEC_U_meas1") (class "Default")
      (node (ref "IC9") (pin "34") (pinfunction "PA0_34") (pintype "bidirectional"))
    )
    (net (code "97") (name "/TEC_U_meas2") (class "Default")
      (node (ref "IC9") (pin "37") (pinfunction "PA3_37") (pintype "bidirectional"))
    )
    (net (code "98") (name "/TEC_U_meas3") (class "Default")
      (node (ref "IC9") (pin "40") (pinfunction "PA4_40") (pintype "bidirectional"))
    )
    (net (code "100") (name "/TIM2_CAPT_IN") (class "Default")
      (node (ref "IC9") (pin "69") (pinfunction "PB10_69") (pintype "bidirectional"))
    )
    (net (code "101") (name "/TIM2_OC4") (class "Default")
      (node (ref "IC9") (pin "70") (pinfunction "PB11_70") (pintype "bidirectional"))
    )
    (net (code "102") (name "/TIM8_OC2") (class "Default")
      (node (ref "IC9") (pin "97") (pinfunction "PC7_97") (pintype "bidirectional"))
    )
    (net (code "103") (name "/TXD") (class "Default")
      (node (ref "IC9") (pin "136") (pinfunction "PB6_136") (pintype "bidirectional"))
      (node (ref "W1") (pin "3") (pinfunction "3_3") (pintype "bidirectional"))
    )
    (net (code "104") (name "/USB_ID") (class "Default")
      (node (ref "IC9") (pin "102") (pinfunction "PA10_102") (pintype "bidirectional"))
    )
    (net (code "105") (name "/USB_N") (class "Default")
      (node (ref "IC9") (pin "103") (pinfunction "PA11_103") (pintype "bidirectional"))
    )
    (net (code "106") (name "/USB_P") (class "Default")
      (node (ref "IC9") (pin "104") (pinfunction "PA12_104") (pintype "bidirectional"))
    )
    (net (code "107") (name "/USB_VBUS") (class "Default")
      (node (ref "R34") (pin "2") (pinfunction "2_2") (pintype "passive"))
    )
    (net (code "108") (name "/U_meas_P3V3") (class "Default")
      (node (ref "C126") (pin "1") (pinfunction "1_1") (pintype "passive"))
      (node (ref "IC9") (pin "19") (pinfunction "PF7_19") (pintype "bidirectional"))
      (node (ref "R92") (pin "1") (pinfunction "1_1") (pintype "passive"))
      (node (ref "R93") (pin "1") (pinfunction "1_1") (pintype "passive"))
    )
    (net (code "109") (name "/U_meas_P5V0") (class "Default")
      (node (ref "C93") (pin "1") (pinfunction "1_1") (pintype "passive"))
      (node (ref "IC9") (pin "26") (pinfunction "PC0_26") (pintype "bidirectional"))
      (node (ref "R82") (pin "2") (pinfunction "2_2") (pintype "passive"))
      (node (ref "R84") (pin "1") (pinfunction "1_1") (pintype "passive"))
    )
    (net (code "110") (name "/U_meas_P12V0") (class "Default")
      (node (ref "C92") (pin "1") (pinfunction "1_1") (pintype "passive"))
      (node (ref "IC9") (pin "28") (pinfunction "PC2_C_28") (pintype "bidirectional"))
      (node (ref "R81") (pin "1") (pinfunction "1_1") (pintype "passive"))
      (node (ref "R83") (pin "1") (pinfunction "1_1") (pintype "passive"))
    )
    (net (code "111") (name "/Vref0") (class "Default")
      (node (ref "IC9") (pin "13") (pinfunction "PF3_13") (pintype "bidirectional"))
    )
    (net (code "112") (name "/Vref1") (class "Default")
      (node (ref "IC9") (pin "14") (pinfunction "PF4_14") (pintype "bidirectional"))
    )
    (net (code "113") (name "/Vref2") (class "Default")
      (node (ref "IC9") (pin "15") (pinfunction "PF5_15") (pintype "bidirectional"))
    )
    (net (code "114") (name "/Vref3") (class "Default")
      (node (ref "IC9") (pin "18") (pinfunction "PF6_18") (pintype "bidirectional"))
    )
    (net (code "116") (name "/~{SHDN}0") (class "Default")
      (node (ref "IC9") (pin "89") (pinfunction "PG4_89") (pintype "bidirectional"))
    )
    (net (code "117") (name "/~{SHDN}1") (class "Default")
      (node (ref "IC9") (pin "90") (pinfunction "PG5_90") (pintype "bidirectional"))
    )
    (net (code "118") (name "/~{SHDN}2") (class "Default")
      (node (ref "IC9") (pin "91") (pinfunction "PG6_91") (pintype "bidirectional"))
    )
    (net (code "119") (name "/~{SHDN}3") (class "Default")
      (node (ref "IC9") (pin "92") (pinfunction "PG7_92") (pintype "bidirectional"))
    )
    (net (code "121") (name "GND") (class "Default")
      (node (ref "C126") (pin "2") (pinfunction "2_2") (pintype "passive"))
      (node (ref "C17") (pin "1") (pinfunction "1_1") (pintype "passive"))
      (node (ref "C18") (pin "1") (pinfunction "1_1") (pintype "passive"))
      (node (ref "C21") (pin "2") (pinfunction "2_2") (pintype "passive"))
      (node (ref "C22") (pin "2") (pinfunction "2_2") (pintype "passive"))
      (node (ref "C23") (pin "2") (pinfunction "2_2") (pintype "passive"))
      (node (ref "C24") (pin "2") (pinfunction "2_2") (pintype "passive"))
      (node (ref "C25") (pin "1") (pinfunction "1_1") (pintype "passive"))
      (node (ref "C28") (pin "1") (pinfunction "1_1") (pintype "passive"))
      (node (ref "C29") (pin "2") (pinfunction "2_2") (pintype "passive"))
      (node (ref "C30") (pin "2") (pinfunction "2_2") (pintype "passive"))
      (node (ref "C31") (pin "2") (pinfunction "2_2") (pintype "passive"))
      (node (ref "C32") (pin "2") (pinfunction "2_2") (pintype "passive"))
      (node (ref "C33") (pin "2") (pinfunction "2_2") (pintype "passive"))
      (node (ref "C35") (pin "2") (pinfunction "2_2") (pintype "passive"))
      (node (ref "C64") (pin "2") (pinfunction "2_2") (pintype "passive"))
      (node (ref "C92") (pin "2") (pinfunction "2_2") (pintype "passive"))
      (node (ref "C93") (pin "2") (pinfunction "2_2") (pintype "passive"))
      (node (ref "C94") (pin "2") (pinfunction "2_2") (pintype "passive"))
      (node (ref "C95") (pin "2") (pinfunction "2_2") (pintype "passive"))
      (node (ref "C96") (pin "2") (pinfunction "2_2") (pintype "passive"))
      (node (ref "C97") (pin "2") (pinfunction "2_2") (pintype "passive"))
      (node (ref "C98") (pin "2") (pinfunction "2_2") (pintype "passive"))
      (node (ref "C99") (pin "2") (pinfunction "2_2") (pintype "passive"))
      (node (ref "D26") (pin "2") (pinfunction "GND_2") (pintype "power_in"))
      (node (ref "IC13") (pin "1") (pinfunction "Vss_1") (pintype "power_in"))
      (node (ref "IC9") (pin "107") (pinfunction "VSS_107") (pintype "power_in"))
      (node (ref "IC9") (pin "120") (pinfunction "VSS_120") (pintype "power_in"))
      (node (ref "IC9") (pin "130") (pinfunction "VSS_130") (pintype "power_in"))
      (node (ref "IC9") (pin "16") (pinfunction "VSS_16") (pintype "power_in"))
      (node (ref "IC9") (pin "31") (pinfunction "VSSA_31") (pintype "power_in"))
      (node (ref "IC9") (pin "38") (pinfunction "VSS_38") (pintype "power_in"))
      (node (ref "IC9") (pin "51") (pinfunction "VSS_51") (pintype "power_in"))
      (node (ref "IC9") (pin "61") (pinfunction "VSS_61") (pintype "power_in"))
      (node (ref "IC9") (pin "83") (pinfunction "VSS_83") (pintype "power_in"))
      (node (ref "IC9") (pin "94") (pinfunction "VSS_94") (pintype "power_in"))
      (node (ref "J21") (pin "3") (pinfunction "3_3") (pintype "bidirectional"))
      (node (ref "J21") (pin "5") (pinfunction "5_5") (pintype "bidirectional"))
      (node (ref "LD11") (pin "1") (pinfunction "C_1") (pintype "passive"))
      (node (ref "LD11") (pin "3") (pinfunction "C_3") (pintype "passive"))
      (node (ref "LD11") (pin "5") (pinfunction "C_5") (pintype "passive"))
      (node (ref "LD11") (pin "7") (pinfunction "C_7") (pintype "passive"))
      (node (ref "LD12") (pin "1") (pinfunction "C_1") (pintype "passive"))
      (node (ref "LD12") (pin "3") (pinfunction "C_3") (pintype "passive"))
      (node (ref "LD12") (pin "5") (pinfunction "C_5") (pintype "passive"))
      (node (ref "LD12") (pin "7") (pinfunction "C_7") (pintype "passive"))
      (node (ref "R106") (pin "2") (pinfunction "2_2") (pintype "passive"))
      (node (ref "R119") (pin "2") (pinfunction "2_2") (pintype "passive"))
      (node (ref "R32") (pin "1") (pinfunction "1_1") (pintype "passive"))
      (node (ref "R63") (pin "2") (pinfunction "2_2") (pintype "passive"))
      (node (ref "R8") (pin "2") (pinfunction "2_2") (pintype "passive"))
      (node (ref "R81") (pin "2") (pinfunction "2_2") (pintype "passive"))
      (node (ref "R84") (pin "2") (pinfunction "2_2") (pintype "passive"))
      (node (ref "R93") (pin "2") (pinfunction "2_2") (pintype "passive"))
      (node (ref "W1") (pin "4") (pinfunction "4_4") (pintype "bidirectional"))
      (node (ref "W2") (pin "5") (pinfunction "5_5") (pintype "bidirectional"))
    )
    (net (code "122") (name "Net-(C17-Pad2)") (class "Default")
      (node (ref "C17") (pin "2") (pinfunction "2_2") (pintype "passive"))
      (node (ref "IC9") (pin "106") (pinfunction "VCAP_106") (pintype "power_in"))
    )
    (net (code "123") (name "Net-(C18-Pad2)") (class "Default")
      (node (ref "C18") (pin "2") (pinfunction "2_2") (pintype "passive"))
      (node (ref "IC9") (pin "71") (pinfunction "VCAP_71") (pintype "power_in"))
    )
    (net (code "124") (name "Net-(IC9A-VBAT)") (class "Default")
      (node (ref "C64") (pin "1") (pinfunction "1_1") (pintype "passive"))
      (node (ref "IC9") (pin "6") (pinfunction "VBAT_6") (pintype "power_in"))
    )
    (net (code "125") (name "Net-(IC9A-VDDA)") (class "Default")
      (node (ref "C23") (pin "1") (pinfunction "1_1") (pintype "passive"))
      (node (ref "C28") (pin "2") (pinfunction "2_2") (pintype "passive"))
      (node (ref "IC9") (pin "33") (pinfunction "VDDA_33") (pintype "power_in"))
      (node (ref "L5") (pin "1") (pinfunction "1_1") (pintype "passive"))
    )
    (net (code "126") (name "Net-(IC9A-VREF+)") (class "Default")
      (node (ref "C24") (pin "1") (pinfunction "1_1") (pintype "passive"))
      (node (ref "C25") (pin "2") (pinfunction "2_2") (pintype "passive"))
      (node (ref "IC9") (pin "32") (pinfunction "VREF+_32") (pintype "power_in"))
      (node (ref "R70") (pin "1") (pinfunction "1_1") (pintype "passive"))
    )
    (net (code "127") (name "Net-(IC9B-PB2)") (class "Default")
      (node (ref "IC9") (pin "48") (pinfunction "PB2_48") (pintype "bidirectional"))
      (node (ref "R32") (pin "2") (pinfunction "2_2") (pintype "passive"))
    )
    (net (code "128") (name "Net-(IC9C-BOOT0)") (class "Default")
      (node (ref "IC9") (pin "138") (pinfunction "BOOT0_138") (pintype "output"))
      (node (ref "JP2") (pin "2") (pinfunction "E2_2") (pintype "passive"))
      (node (ref "R63") (pin "1") (pinfunction "1_1") (pintype "passive"))
    )
    (net (code "129") (name "Net-(IC9C-PA9)") (class "Default")
      (node (ref "IC9") (pin "101") (pinfunction "PA9_101") (pintype "bidirectional"))
      (node (ref "R34") (pin "1") (pinfunction "1_1") (pintype "passive"))
    )
    (net (code "130") (name "Net-(IC9C-PH0-OSC_IN)") (class "Default")
      (node (ref "C21") (pin "1") (pinfunction "1_1") (pintype "passive"))
      (node (ref "IC9") (pin "23") (pinfunction "PH0-OSC_IN_23") (pintype "bidirectional"))
      (node (ref "Q1") (pin "1") (pinfunction "OSC1_1") (pintype "passive"))
    )
    (net (code "131") (name "Net-(IC9C-PH1-OSC_OUT)") (class "Default")
      (node (ref "C22") (pin "1") (pinfunction "1_1") (pintype "passive"))
      (node (ref "IC9") (pin "24") (pinfunction "PH1-OSC_OUT_24") (pintype "bidirectional"))
      (node (ref "Q1") (pin "2") (pinfunction "OSC2_2") (pintype "passive"))
    )
    (net (code "132") (name "Net-(LD11A-A)") (class "Default")
      (node (ref "LD11") (pin "2") (pinfunction "A_2") (pintype "passive"))
      (node (ref "R143") (pin "2") (pinfunction "2_2") (pintype "passive"))
    )
    (net (code "133") (name "Net-(LD11B-A)") (class "Default")
      (node (ref "LD11") (pin "4") (pinfunction "A_4") (pintype "passive"))
      (node (ref "R144") (pin "2") (pinfunction "2_2") (pintype "passive"))
    )
    (net (code "134") (name "Net-(LD11C-A)") (class "Default")
      (node (ref "LD11") (pin "6") (pinfunction "A_6") (pintype "passive"))
      (node (ref "R145") (pin "2") (pinfunction "2_2") (pintype "passive"))
    )
    (net (code "135") (name "Net-(LD11D-A)") (class "Default")
      (node (ref "LD11") (pin "8") (pinfunction "A_8") (pintype "passive"))
      (node (ref "R146") (pin "2") (pinfunction "2_2") (pintype "passive"))
    )
    (net (code "136") (name "Net-(LD12A-A)") (class "Default")
      (node (ref "LD12") (pin "2") (pinfunction "A_2") (pintype "passive"))
      (node (ref "R147") (pin "2") (pinfunction "2_2") (pintype "passive"))
    )
    (net (code "137") (name "Net-(LD12B-A)") (class "Default")
      (node (ref "LD12") (pin "4") (pinfunction "A_4") (pintype "passive"))
      (node (ref "R148") (pin "2") (pinfunction "2_2") (pintype "passive"))
    )
    (net (code "138") (name "Net-(LD12C-A)") (class "Default")
      (node (ref "LD12") (pin "6") (pinfunction "A_6") (pintype "passive"))
      (node (ref "R149") (pin "2") (pinfunction "2_2") (pintype "passive"))
    )
    (net (code "139") (name "Net-(LD12D-A)") (class "Default")
      (node (ref "LD12") (pin "8") (pinfunction "A_8") (pintype "passive"))
      (node (ref "R150") (pin "2") (pinfunction "2_2") (pintype "passive"))
    )
    (net (code "140") (name "P3V0REF") (class "Default")
      (node (ref "R70") (pin "2") (pinfunction "2_2") (pintype "passive"))
    )
    (net (code "141") (name "P3V3") (class "Default")
      (node (ref "C29") (pin "1") (pinfunction "1_1") (pintype "passive"))
      (node (ref "C30") (pin "1") (pinfunction "1_1") (pintype "passive"))
      (node (ref "C31") (pin "1") (pinfunction "1_1") (pintype "passive"))
      (node (ref "C32") (pin "1") (pinfunction "1_1") (pintype "passive"))
      (node (ref "C33") (pin "1") (pinfunction "1_1") (pintype "passive"))
      (node (ref "C35") (pin "1") (pinfunction "1_1") (pintype "passive"))
      (node (ref "C94") (pin "1") (pinfunction "1_1") (pintype "passive"))
      (node (ref "C95") (pin "1") (pinfunction "1_1") (pintype "passive"))
      (node (ref "C96") (pin "1") (pinfunction "1_1") (pintype "passive"))
      (node (ref "C97") (pin "1") (pinfunction "1_1") (pintype "passive"))
      (node (ref "C98") (pin "1") (pinfunction "1_1") (pintype "passive"))
      (node (ref "C99") (pin "1") (pinfunction "1_1") (pintype "passive"))
      (node (ref "D26") (pin "5") (pinfunction "VBUS_5") (pintype "power_in"))
      (node (ref "IC13") (pin "3") (pinfunction "Vcc_3") (pintype "power_in"))
      (node (ref "IC9") (pin "108") (pinfunction "VDD_108") (pintype "power_in"))
      (node (ref "IC9") (pin "121") (pinfunction "VDD_121") (pintype "power_in"))
      (node (ref "IC9") (pin "131") (pinfunction "VDD_131") (pintype "power_in"))
      (node (ref "IC9") (pin "143") (pinfunction "PDR_ON_143") (pintype "power_in"))
      (node (ref "IC9") (pin "144") (pinfunction "VDD_144") (pintype "power_in"))
      (node (ref "IC9") (pin "17") (pinfunction "VDD_17") (pintype "power_in"))
      (node (ref "IC9") (pin "30") (pinfunction "VDD_30") (pintype "power_in"))
      (node (ref "IC9") (pin "39") (pinfunction "VDD_39") (pintype "power_in"))
      (node (ref "IC9") (pin "52") (pinfunction "VDD_52") (pintype "power_in"))
      (node (ref "IC9") (pin "62") (pinfunction "VDD_62") (pintype "power_in"))
      (node (ref "IC9") (pin "72") (pinfunction "VDD_72") (pintype "power_in"))
      (node (ref "IC9") (pin "84") (pinfunction "VDD_84") (pintype "power_in"))
      (node (ref "IC9") (pin "95") (pinfunction "VDD33USB_95") (pintype "power_in"))
      (node (ref "J21") (pin "1") (pinfunction "1_1") (pintype "bidirectional"))
      (node (ref "JP2") (pin "1") (pinfunction "E1_1") (pintype "passive"))
      (node (ref "L5") (pin "2") (pinfunction "2_2") (pintype "passive"))
      (node (ref "R33") (pin "2") (pinfunction "2_2") (pintype "passive"))
      (node (ref "R53") (pin "2") (pinfunction "2_2") (pintype "passive"))
      (node (ref "R61") (pin "2") (pinfunction "2_2") (pintype "passive"))
      (node (ref "R62") (pin "1") (pinfunction "1_1") (pintype "passive"))
      (node (ref "R7") (pin "2") (pinfunction "2_2") (pintype "passive"))
      (node (ref "R92") (pin "2") (pinfunction "2_2") (pintype "passive"))
      (node (ref "W1") (pin "1") (pinfunction "1_1") (pintype "bidirectional"))
      (node (ref "W2") (pin "10") (pinfunction "10_10") (pintype "bidirectional"))
    )
    (net (code "142") (name "P5V0") (class "Default")
      (node (ref "R82") (pin "1") (pinfunction "1_1") (pintype "passive"))
    )
    (net (code "143") (name "P12V0") (class "Default")
      (node (ref "R83") (pin "2") (pinfunction "2_2") (pintype "passive"))
    )
    (net (code "144") (name "unconnected-(IC9C-PD1-Pad115)") (class "Default")
      (node (ref "IC9") (pin "115") (pinfunction "PD1_115") (pintype "bidirectional"))
    )
    (net (code "145") (name "unconnected-(IC9C-PF11-Pad49)") (class "Default")
      (node (ref "IC9") (pin "49") (pinfunction "PF11_49") (pintype "bidirectional"))
    )
    (net (code "146") (name "unconnected-(J21-Pad7)") (class "Default")
      (node (ref "J21") (pin "7") (pinfunction "7_7") (pintype "bidirectional"))
    )
    (net (code "147") (name "unconnected-(J21-Pad9)") (class "Default")
      (node (ref "J21") (pin "9") (pinfunction "9_9") (pintype "bidirectional"))
    )
  )
)
